# DCCShield.net
KiCad netlist of a schematic drawn in EAGLE
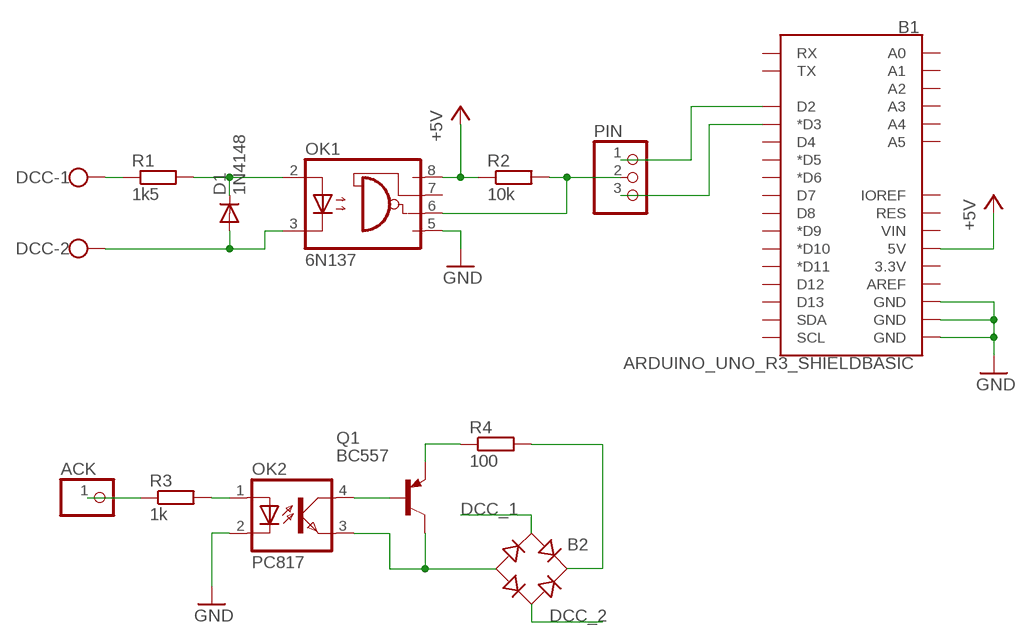
[diagram p0: schematic, sheet 1]

(export (version "E")
  (design (tool "Eeschema 10.0.6"))
  (components
    (comp (ref "ACK")
      (value "PINHD-1X1")
      (footprint "eagle-import:1X01")
      (libsource (lib "eagle-import") (part "PINHD-1X1"))
    )
    (comp (ref "B1")
      (value "ARDUINO_UNO_R3_SHIELDBASIC")
      (footprint "eagle-import:UNO_R3_SHIELD")
      (libsource (lib "eagle-import") (part "ARDUINO_UNO_R3_SHIELDBASIC"))
    )
    (comp (ref "B2")
      (value "RB1A")
      (footprint "eagle-import:RB1A")
      (libsource (lib "eagle-import") (part "RB1A"))
    )
    (comp (ref "D1")
      (value "1N4148")
      (footprint "eagle-import:DO35-10")
      (libsource (lib "eagle-import") (part "1N4148DO35-10"))
    )
    (comp (ref "DCC")
      (value "W237-102")
      (footprint "eagle-import:W237-102")
      (fields (field (name "MPN") "237-102"))
      (libsource (lib "eagle-import") (part "W237-102"))
    )
    (comp (ref "OK1")
      (value "6N137")
      (footprint "eagle-import:DIL08")
      (libsource (lib "eagle-import") (part "6N137"))
    )
    (comp (ref "OK2")
      (value "PC817")
      (footprint "eagle-import:DIL04")
      (fields (field (name "MPN") "PC817X4J000F"))
      (libsource (lib "eagle-import") (part "PC817"))
    )
    (comp (ref "PIN")
      (value "PINHD-1X3")
      (footprint "eagle-import:1X03")
      (libsource (lib "eagle-import") (part "PINHD-1X3"))
    )
    (comp (ref "Q1")
      (value "BC557")
      (footprint "eagle-import:TO92")
      (libsource (lib "eagle-import") (part "BC557"))
    )
    (comp (ref "R1")
      (value "1k5")
      (footprint "eagle-import:0207_10")
      (libsource (lib "eagle-import") (part "R-EU_0207/10"))
    )
    (comp (ref "R2")
      (value "10k")
      (footprint "eagle-import:0207_10")
      (libsource (lib "eagle-import") (part "R-EU_0207/10"))
    )
    (comp (ref "R3")
      (value "1k")
      (footprint "eagle-import:0207_10")
      (libsource (lib "eagle-import") (part "R-EU_0207/10"))
    )
    (comp (ref "R4")
      (value "100")
      (footprint "eagle-import:0207_10")
      (libsource (lib "eagle-import") (part "R-EU_0207/10"))
    )
  )
  (nets
    (net (code "1") (name "+5V") (class "Default")
      (node (ref "B1") (pin "5V") (pinfunction "5V_5V") (pintype "bidirectional"))
      (node (ref "OK1") (pin "8") (pinfunction "VCC_8") (pintype "passive"))
      (node (ref "R2") (pin "1") (pinfunction "1_1") (pintype "passive"))
    )
    (net (code "2") (name "/DCC_1") (class "Default")
      (node (ref "B2") (pin "AC1") (pinfunction "AC1_AC1") (pintype "passive"))
      (node (ref "DCC") (pin "1") (pinfunction "KL_1") (pintype "passive"))
      (node (ref "R1") (pin "1") (pinfunction "1_1") (pintype "passive"))
    )
    (net (code "3") (name "/DCC_2") (class "Default")
      (node (ref "B2") (pin "AC2") (pinfunction "AC2_AC2") (pintype "passive"))
      (node (ref "D1") (pin "A") (pinfunction "A_A") (pintype "passive"))
      (node (ref "DCC") (pin "2") (pinfunction "KL_2") (pintype "passive"))
      (node (ref "OK1") (pin "3") (pinfunction "C_3") (pintype "passive"))
    )
    (net (code "4") (name "GND") (class "Default")
      (node (ref "B1") (pin "GND@0") (pinfunction "GND_GND@0") (pintype "bidirectional"))
      (node (ref "B1") (pin "GND@1") (pinfunction "GND_GND@1") (pintype "bidirectional"))
      (node (ref "B1") (pin "GND@2") (pinfunction "GND_GND@2") (pintype "bidirectional"))
      (node (ref "OK1") (pin "5") (pinfunction "GND_5") (pintype "passive"))
      (node (ref "OK2") (pin "2") (pinfunction "C_2") (pintype "passive"))
    )
    (net (code "5") (name "Net-(ACK-Pad1)") (class "Default")
      (node (ref "ACK") (pin "1") (pinfunction "1_1") (pintype "passive"))
      (node (ref "R3") (pin "1") (pinfunction "1_1") (pintype "passive"))
    )
    (net (code "6") (name "Net-(B1-*D3)") (class "Default")
      (node (ref "B1") (pin "D3") (pinfunction "*D3_D3") (pintype "bidirectional"))
      (node (ref "PIN") (pin "3") (pinfunction "3_3") (pintype "passive"))
    )
    (net (code "7") (name "Net-(B1-PadD2)") (class "Default")
      (node (ref "B1") (pin "D2") (pinfunction "D2_D2") (pintype "bidirectional"))
      (node (ref "PIN") (pin "1") (pinfunction "1_1") (pintype "passive"))
    )
    (net (code "8") (name "Net-(B2-Pad+)") (class "Default")
      (node (ref "B2") (pin "+") (pinfunction "+_+") (pintype "passive"))
      (node (ref "R4") (pin "2") (pinfunction "2_2") (pintype "passive"))
    )
    (net (code "9") (name "Net-(OK1-A)") (class "Default")
      (node (ref "D1") (pin "C") (pinfunction "C_C") (pintype "passive"))
      (node (ref "OK1") (pin "2") (pinfunction "A_2") (pintype "passive"))
      (node (ref "R1") (pin "2") (pinfunction "2_2") (pintype "passive"))
    )
    (net (code "10") (name "Net-(OK1-VO)") (class "Default")
      (node (ref "OK1") (pin "6") (pinfunction "VO_6") (pintype "passive"))
      (node (ref "PIN") (pin "2") (pinfunction "2_2") (pintype "passive"))
      (node (ref "R2") (pin "2") (pinfunction "2_2") (pintype "passive"))
    )
    (net (code "11") (name "Net-(OK2-A)") (class "Default")
      (node (ref "OK2") (pin "1") (pinfunction "A_1") (pintype "passive"))
      (node (ref "R3") (pin "2") (pinfunction "2_2") (pintype "passive"))
    )
    (net (code "12") (name "Net-(OK2-COL)") (class "Default")
      (node (ref "OK2") (pin "4") (pinfunction "COL_4") (pintype "passive"))
      (node (ref "Q1") (pin "2") (pinfunction "B_2") (pintype "passive"))
    )
    (net (code "13") (name "Net-(OK2-EMIT)") (class "Default")
      (node (ref "B2") (pin "-") (pinfunction "-_-") (pintype "passive"))
      (node (ref "OK2") (pin "3") (pinfunction "EMIT_3") (pintype "passive"))
      (node (ref "Q1") (pin "3") (pinfunction "C_3") (pintype "passive"))
    )
    (net (code "14") (name "Net-(Q1-E)") (class "Default")
      (node (ref "Q1") (pin "1") (pinfunction "E_1") (pintype "passive"))
      (node (ref "R4") (pin "1") (pinfunction "1_1") (pintype "passive"))
    )
    (net (code "15") (name "unconnected-(B1-*D5-PadD5)") (class "Default")
      (node (ref "B1") (pin "D5") (pinfunction "*D5_D5") (pintype "bidirectional"))
    )
    (net (code "16") (name "unconnected-(B1-*D6-PadD6)") (class "Default")
      (node (ref "B1") (pin "D6") (pinfunction "*D6_D6") (pintype "bidirectional"))
    )
    (net (code "17") (name "unconnected-(B1-*D9-PadD9)") (class "Default")
      (node (ref "B1") (pin "D9") (pinfunction "*D9_D9") (pintype "bidirectional"))
    )
    (net (code "18") (name "unconnected-(B1-*D10-PadD10)") (class "Default")
      (node (ref "B1") (pin "D10") (pinfunction "*D10_D10") (pintype "bidirectional"))
    )
    (net (code "19") (name "unconnected-(B1-*D11-PadD11)") (class "Default")
      (node (ref "B1") (pin "D11") (pinfunction "*D11_D11") (pintype "bidirectional"))
    )
    (net (code "20") (name "unconnected-(B1-Pad3.3V)") (class "Default")
      (node (ref "B1") (pin "3.3V") (pinfunction "3.3V_3.3V") (pintype "bidirectional"))
    )
    (net (code "21") (name "unconnected-(B1-PadA0)") (class "Default")
      (node (ref "B1") (pin "A0") (pinfunction "A0_A0") (pintype "bidirectional"))
    )
    (net (code "22") (name "unconnected-(B1-PadA1)") (class "Default")
      (node (ref "B1") (pin "A1") (pinfunction "A1_A1") (pintype "bidirectional"))
    )
    (net (code "23") (name "unconnected-(B1-PadA2)") (class "Default")
      (node (ref "B1") (pin "A2") (pinfunction "A2_A2") (pintype "bidirectional"))
    )
    (net (code "24") (name "unconnected-(B1-PadA3)") (class "Default")
      (node (ref "B1") (pin "A3") (pinfunction "A3_A3") (pintype "bidirectional"))
    )
    (net (code "25") (name "unconnected-(B1-PadA4)") (class "Default")
      (node (ref "B1") (pin "A4") (pinfunction "A4_A4") (pintype "bidirectional"))
    )
    (net (code "26") (name "unconnected-(B1-PadA5)") (class "Default")
      (node (ref "B1") (pin "A5") (pinfunction "A5_A5") (pintype "bidirectional"))
    )
    (net (code "27") (name "unconnected-(B1-PadAREF)") (class "Default")
      (node (ref "B1") (pin "AREF") (pinfunction "AREF_AREF") (pintype "bidirectional"))
    )
    (net (code "28") (name "unconnected-(B1-PadD4)") (class "Default")
      (node (ref "B1") (pin "D4") (pinfunction "D4_D4") (pintype "bidirectional"))
    )
    (net (code "29") (name "unconnected-(B1-PadD7)") (class "Default")
      (node (ref "B1") (pin "D7") (pinfunction "D7_D7") (pintype "bidirectional"))
    )
    (net (code "30") (name "unconnected-(B1-PadD8)") (class "Default")
      (node (ref "B1") (pin "D8") (pinfunction "D8_D8") (pintype "bidirectional"))
    )
    (net (code "31") (name "unconnected-(B1-PadD12)") (class "Default")
      (node (ref "B1") (pin "D12") (pinfunction "D12_D12") (pintype "bidirectional"))
    )
    (net (code "32") (name "unconnected-(B1-PadD13)") (class "Default")
      (node (ref "B1") (pin "D13") (pinfunction "D13_D13") (pintype "bidirectional"))
    )
    (net (code "33") (name "unconnected-(B1-PadIOREF)") (class "Default")
      (node (ref "B1") (pin "IOREF") (pinfunction "IOREF_IOREF") (pintype "bidirectional"))
    )
    (net (code "34") (name "unconnected-(B1-PadRES)") (class "Default")
      (node (ref "B1") (pin "RES") (pinfunction "RES_RES") (pintype "bidirectional"))
    )
    (net (code "35") (name "unconnected-(B1-PadRX)") (class "Default")
      (node (ref "B1") (pin "RX") (pinfunction "RX_RX") (pintype "bidirectional"))
    )
    (net (code "36") (name "unconnected-(B1-PadSCL)") (class "Default")
      (node (ref "B1") (pin "SCL") (pinfunction "SCL_SCL") (pintype "bidirectional"))
    )
    (net (code "37") (name "unconnected-(B1-PadSDA)") (class "Default")
      (node (ref "B1") (pin "SDA") (pinfunction "SDA_SDA") (pintype "bidirectional"))
    )
    (net (code "38") (name "unconnected-(B1-PadTX)") (class "Default")
      (node (ref "B1") (pin "TX") (pinfunction "TX_TX") (pintype "bidirectional"))
    )
    (net (code "39") (name "unconnected-(B1-PadVIN)") (class "Default")
      (node (ref "B1") (pin "VIN") (pinfunction "VIN_VIN") (pintype "bidirectional"))
    )
    (net (code "40") (name "unconnected-(OK1-VE-Pad7)") (class "Default")
      (node (ref "OK1") (pin "7") (pinfunction "VE_7") (pintype "passive"))
    )
  )
)
